# POE_SI3404.net
KiCad netlist of a schematic drawn in Altium Designer
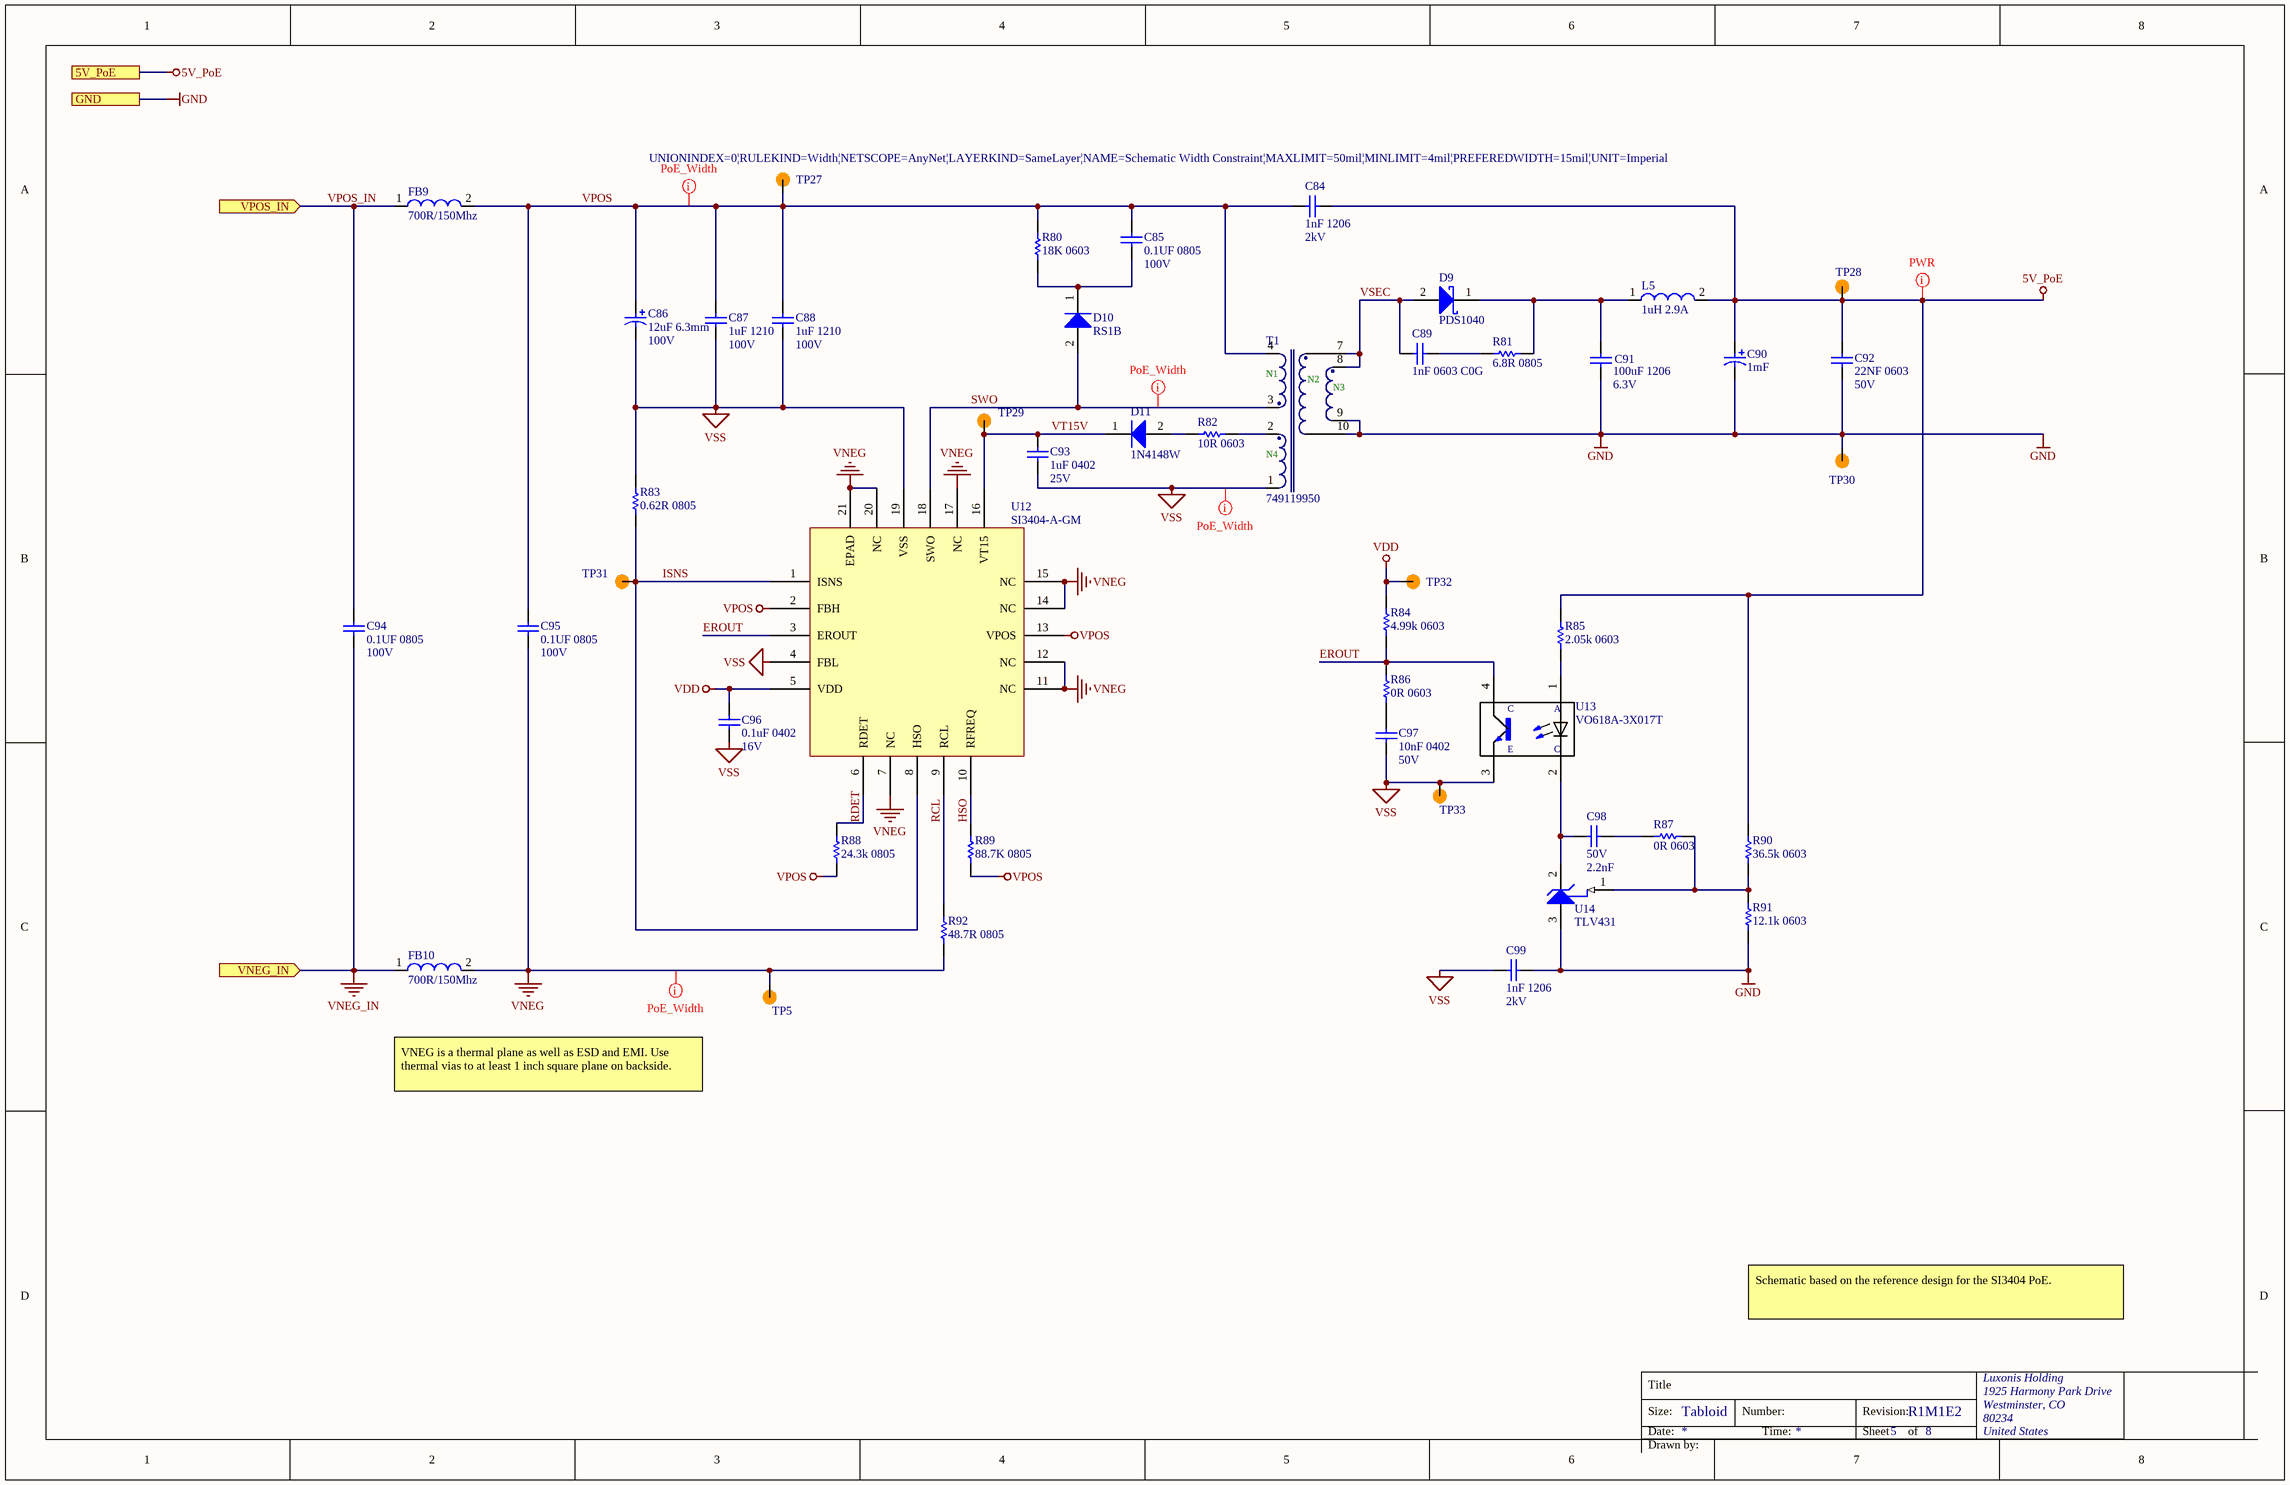
[diagram p0: POE_SI3404.SchDoc]

(export (version "E")
  (design (tool "Eeschema 10.0.6"))
  (components
    (comp (ref "C84")
      (value "1nF 1206")
      (footprint "CAP_Altium_Vault_Generic:CAPC1206(3216)190_N")
      (description "CAP CER 1000PF 2KV X7R 1206")
      (fields (field (name "TOLERANCE") "10%") (field (name "VOLTAGE RATING (DC)") "2kV"))
      (libsource (lib "PCBProject") (part "C1206C102KGRACTU"))
    )
    (comp (ref "C85")
      (value "0.1UF 0805")
      (footprint "CAP_Altium_Vault_Generic:CAPC0805(2012)145_N")
      (description "CAP CER 0.1UF 100V X7R 0805")
      (fields (field (name "TOLERANCE") "10%") (field (name "VOLTAGE RATING") "100V"))
      (libsource (lib "BW2098POE") (part "CL21B104KCFNNNE"))
    )
    (comp (ref "C86")
      (value "12uF 6.3mm")
      (footprint "BW2098POE:EEU-FC2A120")
      (description "CAP ALUM 12UF 20% 100V RADIAL")
      (fields (field (name "TOLERANCE") "20%") (field (name "VOLTAGE") "100V"))
      (libsource (lib "BW2098POE") (part "EEU-FC2A120"))
    )
    (comp (ref "C87")
      (value "1uF 1210")
      (footprint "CAP_Altium_Vault_Generic:CAPC1210(3225)280_N")
      (description "CAP CER 1UF 100V X7R 1210")
      (fields (field (name "TOLERANCE") "10%") (field (name "VOLTAGE RATING") "100V"))
      (libsource (lib "PCBProject") (part "CL32B105KCJNNNE"))
    )
    (comp (ref "C88")
      (value "1uF 1210")
      (footprint "CAP_Altium_Vault_Generic:CAPC1210(3225)280_N")
      (description "CAP CER 1UF 100V X7R 1210")
      (fields (field (name "TOLERANCE") "10%") (field (name "VOLTAGE RATING") "100V"))
      (libsource (lib "PCBProject") (part "CL32B105KCJNNNE"))
    )
    (comp (ref "C89")
      (value "1nF 0603 C0G")
      (footprint "CAP_Altium_Vault_Generic:CAPC0603(1608)100_N")
      (description "CAP CER 1000PF 50V C0G/NP0 0603")
      (fields
        (field (name "MANUFACTURER") "Murata")
        (field (name "MANUFACTURER PART NUMBER") "GRM1885C1H102FA01D")
      )
      (libsource (lib "LuxonisMaster") (part "GRM1885C1H102FA01D"))
    )
    (comp (ref "C90")
      (value "1mF")
      (footprint "ECA-0JM102")
      (description "CAP ALUM 1000UF 6.3V RADIAL 20%")
      (fields (field (name "TOLERANCE") "20%") (field (name "Comment") "ECA-0JM102"))
      (libsource (lib "Luxonis LLC") (part "EEU-FC2A120"))
    )
    (comp (ref "C91")
      (value "100uF 1206")
      (footprint "CAP_Altium_Vault_Generic:CAPC1206(3216)190_N")
      (description "CAP CER 100UF 6.3V X5R 1206")
      (fields (field (name "TOLERANCE") "20%") (field (name "VOLTAGE") "6.3V"))
      (libsource (lib "PCBProject") (part "CL31A107MQHNNNE"))
    )
    (comp (ref "C92")
      (value "22NF 0603")
      (footprint "CAP_Altium_Vault_Generic:CAPC0603(1608)100_N")
      (description "CAP CER 0.022UF 50V X7R 0603")
      (fields (field (name "TOLERANCE") "10%") (field (name "VOLTAGE") "50V"))
      (libsource (lib "LuxonisMaster") (part "C0603C223K5RACTU"))
    )
    (comp (ref "C93")
      (value "1uF 0402")
      (footprint "CAP_Altium_Vault_Generic:CAPC0402(1005)70_N")
      (description "CAP CER 1UF 25V X5R 0402 10%")
      (fields
        (field (name "TOLERANCE") "10%")
        (field (name "VOLTAGE") "25V")
        (field (name "VOLTAGE RATING") "25V")
      )
      (libsource (lib "LuxonisMaster") (part "GRM155R61E105KA12D"))
    )
    (comp (ref "C94")
      (value "0.1UF 0805")
      (footprint "CAP_Altium_Vault_Generic:CAPC0805(2012)145_N")
      (description "CAP CER 0.1UF 100V X7R 0805")
      (fields (field (name "TOLERANCE") "10%") (field (name "VOLTAGE RATING") "100V"))
      (libsource (lib "PCBProject") (part "CL21B104KCFNNNE"))
    )
    (comp (ref "C95")
      (value "0.1UF 0805")
      (footprint "CAP_Altium_Vault_Generic:CAPC0805(2012)145_N")
      (description "CAP CER 0.1UF 100V X7R 0805")
      (fields (field (name "TOLERANCE") "10%") (field (name "VOLTAGE RATING") "100V"))
      (libsource (lib "PCBProject") (part "CL21B104KCFNNNE"))
    )
    (comp (ref "C96")
      (value "0.1uF 0402")
      (footprint "CAP_Altium_Vault_Generic:CAPC0402(1005)60_N")
      (description "CAP CER 0.1UF 16V X7R 0402")
      (fields (field (name "TOLERANCE") "10%") (field (name "VOLTAGE RATING") "16V"))
      (libsource (lib "PCBProject") (part "CL05B104KO5NFNC"))
    )
    (comp (ref "C97")
      (value "10nF 0402")
      (footprint "CAP_Altium_Vault_Generic:CAPC0402(1005)60_N")
      (description "CAP CER 10000PF 50V X7R 0402")
      (fields
        (field (name "TOLERANCE") "10%")
        (field (name "VOLTAGE") "25V")
        (field (name "VOLTAGE RATING") "50V")
      )
      (libsource (lib "LuxonisMaster") (part "GRM155R71H103KA88D"))
    )
    (comp (ref "C98")
      (value "2.2nF")
      (footprint "CAPC0603(1608)100_N")
      (description "CAP CER 2200PF 50V C0G 0603 5%")
      (fields
        (field (name "VOLTAGE RATING") "50V")
        (field (name "TOLERANCE") "5%")
        (field (name "Comment") "GRM1885C1H222JA01D")
      )
      (libsource (lib "Luxonis LLC") (part "GRM188R61C475KAAJD"))
    )
    (comp (ref "C99")
      (value "1nF 1206")
      (footprint "CAP_Altium_Vault_Generic:CAPC1206(3216)190_N")
      (description "CAP CER 1000PF 2KV X7R 1206")
      (fields (field (name "TOLERANCE") "10%") (field (name "VOLTAGE RATING (DC)") "2kV"))
      (libsource (lib "PCBProject") (part "C1206C102KGRACTU"))
    )
    (comp (ref "D9")
      (value "PDS1040")
      (footprint "BW2098POE:PDS1040-13")
      (description "DIODE SCHOTTKY 40V 10A POWERDI5")
      (libsource (lib "PCBProject") (part "PDS1040-13"))
    )
    (comp (ref "D10")
      (value "RS1B")
      (footprint "BW2098POE:RS1B")
      (description "DIODE GEN PURP 100V 1A SMA")
      (libsource (lib "BW2098POE") (part "RS1B"))
    )
    (comp (ref "D11")
      (value "1N4148W")
      (footprint "BW2098POE:1N4148W-7-F")
      (description "DIODE GEN PURP 100V 300MA SOD123")
      (fields (field (name "VOLTAGE") "100V"))
      (libsource (lib "PCBProject") (part "1N4148W-7-F"))
    )
    (comp (ref "FB9")
      (value "700R/150Mhz")
      (footprint "BW2098POE:742792040")
      (description "FERRITE BEAD 600 OHM 0805 1LN")
      (fields (field (name "TOLERANCE") "25%"))
      (libsource (lib "BW2098POE") (part "742792040"))
    )
    (comp (ref "FB10")
      (value "700R/150Mhz")
      (footprint "BW2098POE:742792040")
      (description "FERRITE BEAD 600 OHM 0805 1LN")
      (fields (field (name "TOLERANCE") "25%"))
      (libsource (lib "BW2098POE") (part "742792040"))
    )
    (comp (ref "L5")
      (value "1uH 2.9A")
      (footprint "BW2098POE:DO1608C-102MLx")
      (description "IND POWER WIREWOUND 1uH 20% 100KHz FERRITE 2.7A")
      (fields (field (name "TOLERANCE") "20%"))
      (libsource (lib "PCBProject") (part "DO1608C-102ML"))
    )
    (comp (ref "R80")
      (value "18K 0603")
      (footprint "RES_Altium_Vault_Generic:RESC0603(1608)_N")
      (description "RES SMD 18K OHM 5% 1/10W 0603")
      (fields (field (name "TOLERANCE") "5%"))
      (libsource (lib "BW2098POE") (part "RC0603JR-0718KL"))
    )
    (comp (ref "R81")
      (value "6.8R 0805")
      (footprint "RES_Altium_Vault_Generic:RESC0805(2012)_N")
      (description "RES SMD 6.8 OHM 1% 1/8W 0805")
      (fields (field (name "TOLERANCE") "1%"))
      (libsource (lib "BW2098POE") (part "RC0805FR-076R8L"))
    )
    (comp (ref "R82")
      (value "10R 0603")
      (footprint "RES_Altium_Vault_Generic:RESC0603(1608)_N")
      (description "RES SMD 10 OHM 1% 1/10W 0603")
      (fields (field (name "TOLERANCE") "1%"))
      (libsource (lib "PCBProject") (part "CRCW060310R0FKEA"))
    )
    (comp (ref "R83")
      (value "0.62R 0805")
      (footprint "RES_Altium_Vault_Generic:RESC0805(2012)_N")
      (description "RES SMD 620 MOHM 1% 1/8W 0805")
      (fields (field (name "TOLERANCE") "1%"))
      (libsource (lib "BW2098POE") (part "RL0805FR-070R62L"))
    )
    (comp (ref "R84")
      (value "4.99k 0603")
      (footprint "RES_Altium_Vault_Generic:RESC0603(1608)_N")
      (description "RES SMD 4.99K OHM 1% 1/10W 0603")
      (fields (field (name "TOLERANCE") "1%"))
      (libsource (lib "PCBProject") (part "RC0603FR-074K99L"))
    )
    (comp (ref "R85")
      (value "2.05k 0603")
      (footprint "RES_Altium_Vault_Generic:RESC0603(1608)_N")
      (description "RES SMD 2.05K OHM 1% 1/10W 0603")
      (fields (field (name "TOLERANCE") "1%"))
      (libsource (lib "PCBProject") (part "RC0603FR-072K05L"))
    )
    (comp (ref "R86")
      (value "0R 0603")
      (footprint "RES_Altium_Vault_Generic:RESC0603(1608)_N")
      (description "RES SMD 0.0R OHM 1% 1/10W 0603")
      (fields (field (name "TOLERANCE") "5%"))
      (libsource (lib "LuxonisMaster") (part "CRCW06030000Z0EA"))
    )
    (comp (ref "R87")
      (value "0R 0603")
      (footprint "RES_Altium_Vault_Generic:RESC0603(1608)_N")
      (description "RES SMD 0.0R OHM 1% 1/10W 0603")
      (fields (field (name "TOLERANCE") "5%"))
      (libsource (lib "LuxonisMaster") (part "CRCW06030000Z0EA"))
    )
    (comp (ref "R88")
      (value "24.3k 0805")
      (footprint "RES_Altium_Vault_Generic:RESC0805(2012)_N")
      (description "RES SMD 24.3K OHM 1% 1/8W 0805")
      (fields (field (name "TOLERANCE") "1%"))
      (libsource (lib "PCBProject") (part "CRCW080524K3FKEA"))
    )
    (comp (ref "R89")
      (value "88.7K 0805")
      (footprint "RES_Altium_Vault_Generic:RESC0805(2012)_N")
      (description "RES SMD 88.7K OHM 1% 1/8W 0805")
      (fields (field (name "TOLERANCE") "1%"))
      (libsource (lib "BW2098POE") (part "CRCW080588K7FKEA"))
    )
    (comp (ref "R90")
      (value "36.5k 0603")
      (footprint "RES_Altium_Vault_Generic:RESC0603(1608)_N")
      (description "RES SMD 36.5K OHM 1% 1/10W 0603")
      (fields (field (name "TOLERANCE") "1%"))
      (libsource (lib "PCBProject") (part "RC0603FR-0736K5L"))
    )
    (comp (ref "R91")
      (value "12.1k 0603")
      (footprint "RES_Altium_Vault_Generic:RESC0603(1608)_N")
      (description "RES SMD 12.1K OHM 1% 1/10W 0603")
      (fields (field (name "TOLERANCE") "1%"))
      (libsource (lib "PCBProject") (part "RC0603FR-0712K1L"))
    )
    (comp (ref "R92")
      (value "48.7R 0805")
      (footprint "RES_Altium_Vault_Generic:RESC0805(2012)_N")
      (description "RES SMD 48.7 OHM 1% 1/8W 0805")
      (fields (field (name "TOLERANCE") "1%"))
      (libsource (lib "PCBProject") (part "RC0805FR-0748R7L"))
    )
    (comp (ref "T1")
      (value "749119950")
      (footprint "BW2098POE:749119950")
      (description "TRANS FLYBACK POE 127UH SMD")
      (libsource (lib "BW2098POE") (part "749119950"))
    )
    (comp (ref "TP5")
      (value "TP100_200_NS")
      (footprint "TP075_150_NS")
      (libsource (lib "Luxonis LLC") (part "TEST_POINT"))
    )
    (comp (ref "TP27")
      (value "TP100_200_NS")
      (footprint "TP075_150_NS")
      (libsource (lib "Luxonis LLC") (part "TEST_POINT"))
    )
    (comp (ref "TP28")
      (value "TP100_200_NS")
      (footprint "TP075_150_NS")
      (libsource (lib "Luxonis LLC") (part "TEST_POINT"))
    )
    (comp (ref "TP29")
      (value "TP100_200_NS")
      (footprint "TP075_150_NS")
      (libsource (lib "Luxonis LLC") (part "TEST_POINT"))
    )
    (comp (ref "TP30")
      (value "TP100_200_NS")
      (footprint "TP075_150_NS")
      (libsource (lib "Luxonis LLC") (part "TEST_POINT"))
    )
    (comp (ref "TP31")
      (value "TP100_200_NS")
      (footprint "TP075_150_NS")
      (libsource (lib "Luxonis LLC") (part "TEST_POINT"))
    )
    (comp (ref "TP32")
      (value "TP100_200_NS")
      (footprint "TP075_150_NS")
      (libsource (lib "Luxonis LLC") (part "TEST_POINT"))
    )
    (comp (ref "TP33")
      (value "TP100_200_NS")
      (footprint "TP075_150_NS")
      (libsource (lib "Luxonis LLC") (part "TEST_POINT"))
    )
    (comp (ref "U12")
      (value "SI3404-A-GM")
      (footprint "BW2098POE:Si3404-A-GM")
      (description "IC POE CNTRL 1 CHANNEL 20QFN")
      (libsource (lib "BW2098POE") (part "SI3404-A-GM"))
    )
    (comp (ref "U13")
      (value "VO618A-3X017T")
      (footprint "PCBProject:VO618A-3X017T")
      (description "OPTOISOLATOR 5.3KV TRANS 4-SMD")
      (libsource (lib "BW2098POE") (part "VO618A-3X017T"))
    )
    (comp (ref "U14")
      (value "TLV431")
      (footprint "PCBProject:TLV431BCDBZR")
      (description "IC VREF SHUNT ADJ SOT23-3")
      (fields (field (name "TOLERANCE") "0.5%"))
      (libsource (lib "BW2098POE") (part "TLV431BCDBZR"))
    )
  )
  (nets
    (net (code "1") (name "/EROUT") (class "Default")
      (node (ref "R84") (pin "1") (pinfunction "1_1") (pintype "passive"))
      (node (ref "R86") (pin "2") (pinfunction "2_2") (pintype "passive"))
      (node (ref "U12") (pin "3") (pinfunction "EROUT_3") (pintype "passive"))
      (node (ref "U13") (pin "4") (pinfunction "CO_4") (pintype "passive"))
    )
    (net (code "2") (name "/HSO") (class "Default")
      (node (ref "R89") (pin "2") (pinfunction "2_2") (pintype "passive"))
      (node (ref "U12") (pin "10") (pinfunction "RFREQ_10") (pintype "passive"))
    )
    (net (code "3") (name "/ISNS") (class "Default")
      (node (ref "R83") (pin "1") (pinfunction "1_1") (pintype "passive"))
      (node (ref "TP31") (pin "1") (pintype "passive"))
      (node (ref "U12") (pin "1") (pinfunction "ISNS_1") (pintype "passive"))
      (node (ref "U12") (pin "8") (pinfunction "HSO_8") (pintype "passive"))
    )
    (net (code "4") (name "/RCL") (class "Default")
      (node (ref "R92") (pin "2") (pinfunction "2_2") (pintype "passive"))
      (node (ref "U12") (pin "9") (pinfunction "RCL_9") (pintype "passive"))
    )
    (net (code "5") (name "/RDET") (class "Default")
      (node (ref "R88") (pin "2") (pinfunction "2_2") (pintype "passive"))
      (node (ref "U12") (pin "6") (pinfunction "RDET_6") (pintype "passive"))
    )
    (net (code "6") (name "/SWO") (class "Default")
      (node (ref "D10") (pin "2") (pinfunction "A_2") (pintype "passive"))
      (node (ref "T1") (pin "3") (pinfunction "3_3") (pintype "passive"))
      (node (ref "U12") (pin "18") (pinfunction "SWO_18") (pintype "passive"))
    )
    (net (code "7") (name "/VPOS_IN") (class "Default")
      (node (ref "C94") (pin "2") (pinfunction "2_2") (pintype "passive"))
      (node (ref "FB9") (pin "1") (pinfunction "1_1") (pintype "passive"))
    )
    (net (code "8") (name "/VSEC") (class "Default")
      (node (ref "C89") (pin "2") (pinfunction "2_2") (pintype "passive"))
      (node (ref "D9") (pin "2") (pinfunction "A_2") (pintype "passive"))
      (node (ref "T1") (pin "7") (pinfunction "7_7") (pintype "passive"))
      (node (ref "T1") (pin "8") (pinfunction "8_8") (pintype "passive"))
    )
    (net (code "9") (name "/VT15V") (class "Default")
      (node (ref "C93") (pin "2") (pinfunction "2_2") (pintype "passive"))
      (node (ref "D11") (pin "1") (pinfunction "K_1") (pintype "passive"))
      (node (ref "TP29") (pin "1") (pintype "passive"))
      (node (ref "U12") (pin "16") (pinfunction "VT15_16") (pintype "passive"))
    )
    (net (code "10") (name "5V_PoE") (class "Default")
      (node (ref "C84") (pin "2") (pinfunction "2_2") (pintype "passive"))
      (node (ref "C90") (pin "1") (pinfunction "1_1") (pintype "passive"))
      (node (ref "C92") (pin "2") (pinfunction "2_2") (pintype "passive"))
      (node (ref "L5") (pin "2") (pinfunction "2_2") (pintype "passive"))
      (node (ref "R85") (pin "2") (pinfunction "2_2") (pintype "passive"))
      (node (ref "R90") (pin "2") (pinfunction "2_2") (pintype "passive"))
      (node (ref "TP28") (pin "1") (pintype "passive"))
    )
    (net (code "11") (name "GND") (class "Default")
      (node (ref "C90") (pin "2") (pinfunction "2_2") (pintype "passive"))
      (node (ref "C91") (pin "1") (pinfunction "1_1") (pintype "passive"))
      (node (ref "C92") (pin "1") (pinfunction "1_1") (pintype "passive"))
      (node (ref "C99") (pin "2") (pinfunction "2_2") (pintype "passive"))
      (node (ref "R91") (pin "1") (pinfunction "1_1") (pintype "passive"))
      (node (ref "T1") (pin "10") (pinfunction "10_10") (pintype "passive"))
      (node (ref "T1") (pin "9") (pinfunction "9_9") (pintype "passive"))
      (node (ref "TP30") (pin "1") (pintype "passive"))
      (node (ref "U14") (pin "3") (pinfunction "ANODE_3") (pintype "passive"))
    )
    (net (code "12") (name "Net-(C89-Pad1)") (class "Default")
      (node (ref "C89") (pin "1") (pinfunction "1_1") (pintype "passive"))
      (node (ref "R81") (pin "1") (pinfunction "1_1") (pintype "passive"))
    )
    (net (code "13") (name "Net-(C97-Pad2)") (class "Default")
      (node (ref "C97") (pin "2") (pinfunction "2_2") (pintype "passive"))
      (node (ref "R86") (pin "1") (pinfunction "1_1") (pintype "passive"))
    )
    (net (code "14") (name "Net-(C98-Pad2)") (class "Default")
      (node (ref "C98") (pin "2") (pinfunction "2_2") (pintype "passive"))
      (node (ref "R87") (pin "2") (pinfunction "2_2") (pintype "passive"))
    )
    (net (code "15") (name "Net-(D9-K)") (class "Default")
      (node (ref "C91") (pin "2") (pinfunction "2_2") (pintype "passive"))
      (node (ref "D9") (pin "1") (pinfunction "K_1") (pintype "passive"))
      (node (ref "L5") (pin "1") (pinfunction "1_1") (pintype "passive"))
      (node (ref "R81") (pin "2") (pinfunction "2_2") (pintype "passive"))
    )
    (net (code "16") (name "Net-(D10-K)") (class "Default")
      (node (ref "C85") (pin "1") (pinfunction "1_1") (pintype "passive"))
      (node (ref "D10") (pin "1") (pinfunction "K_1") (pintype "passive"))
      (node (ref "R80") (pin "1") (pinfunction "1_1") (pintype "passive"))
    )
    (net (code "17") (name "Net-(D11-A)") (class "Default")
      (node (ref "D11") (pin "2") (pinfunction "A_2") (pintype "passive"))
      (node (ref "R82") (pin "1") (pinfunction "1_1") (pintype "passive"))
    )
    (net (code "18") (name "Net-(R82-Pad2)") (class "Default")
      (node (ref "R82") (pin "2") (pinfunction "2_2") (pintype "passive"))
      (node (ref "T1") (pin "2") (pinfunction "2_2") (pintype "passive"))
    )
    (net (code "19") (name "Net-(U13-A)") (class "Default")
      (node (ref "R85") (pin "1") (pinfunction "1_1") (pintype "passive"))
      (node (ref "U13") (pin "1") (pinfunction "A_1") (pintype "passive"))
    )
    (net (code "20") (name "Net-(U13-C)") (class "Default")
      (node (ref "C98") (pin "1") (pinfunction "1_1") (pintype "passive"))
      (node (ref "U13") (pin "2") (pinfunction "C_2") (pintype "passive"))
      (node (ref "U14") (pin "2") (pinfunction "CATHODE_2") (pintype "passive"))
    )
    (net (code "21") (name "Net-(U14-REF)") (class "Default")
      (node (ref "R87") (pin "1") (pinfunction "1_1") (pintype "passive"))
      (node (ref "R90") (pin "1") (pinfunction "1_1") (pintype "passive"))
      (node (ref "R91") (pin "2") (pinfunction "2_2") (pintype "passive"))
      (node (ref "U14") (pin "1") (pinfunction "REF_1") (pintype "input"))
    )
    (net (code "22") (name "VDD") (class "Default")
      (node (ref "C96") (pin "2") (pinfunction "2_2") (pintype "passive"))
      (node (ref "R84") (pin "2") (pinfunction "2_2") (pintype "passive"))
      (node (ref "TP32") (pin "1") (pintype "passive"))
      (node (ref "U12") (pin "5") (pinfunction "VDD_5") (pintype "passive"))
    )
    (net (code "23") (name "VNEG") (class "Default")
      (node (ref "C95") (pin "1") (pinfunction "1_1") (pintype "passive"))
      (node (ref "FB10") (pin "2") (pinfunction "2_2") (pintype "passive"))
      (node (ref "R92") (pin "1") (pinfunction "1_1") (pintype "passive"))
      (node (ref "TP5") (pin "1") (pintype "passive"))
      (node (ref "U12") (pin "11") (pinfunction "NC_11") (pintype "passive"))
      (node (ref "U12") (pin "12") (pinfunction "NC_12") (pintype "passive"))
      (node (ref "U12") (pin "14") (pinfunction "NC_14") (pintype "passive"))
      (node (ref "U12") (pin "15") (pinfunction "NC_15") (pintype "passive"))
      (node (ref "U12") (pin "17") (pinfunction "NC_17") (pintype "passive"))
      (node (ref "U12") (pin "20") (pinfunction "NC_20") (pintype "passive"))
      (node (ref "U12") (pin "21") (pinfunction "EPAD_21") (pintype "passive"))
      (node (ref "U12") (pin "7") (pinfunction "NC_7") (pintype "passive"))
    )
    (net (code "24") (name "VNEG_IN") (class "Default")
      (node (ref "C94") (pin "1") (pinfunction "1_1") (pintype "passive"))
      (node (ref "FB10") (pin "1") (pinfunction "1_1") (pintype "passive"))
    )
    (net (code "25") (name "VPOS") (class "Default")
      (node (ref "C84") (pin "1") (pinfunction "1_1") (pintype "passive"))
      (node (ref "C85") (pin "2") (pinfunction "2_2") (pintype "passive"))
      (node (ref "C86") (pin "1") (pinfunction "1_1") (pintype "passive"))
      (node (ref "C87") (pin "2") (pinfunction "2_2") (pintype "passive"))
      (node (ref "C88") (pin "2") (pinfunction "2_2") (pintype "passive"))
      (node (ref "C95") (pin "2") (pinfunction "2_2") (pintype "passive"))
      (node (ref "FB9") (pin "2") (pinfunction "2_2") (pintype "passive"))
      (node (ref "R80") (pin "2") (pinfunction "2_2") (pintype "passive"))
      (node (ref "R88") (pin "1") (pinfunction "1_1") (pintype "passive"))
      (node (ref "R89") (pin "1") (pinfunction "1_1") (pintype "passive"))
      (node (ref "T1") (pin "4") (pinfunction "4_4") (pintype "passive"))
      (node (ref "TP27") (pin "1") (pintype "passive"))
      (node (ref "U12") (pin "13") (pinfunction "VPOS_13") (pintype "passive"))
      (node (ref "U12") (pin "2") (pinfunction "FBH_2") (pintype "passive"))
    )
    (net (code "26") (name "VSS") (class "Default")
      (node (ref "C86") (pin "2") (pinfunction "2_2") (pintype "passive"))
      (node (ref "C87") (pin "1") (pinfunction "1_1") (pintype "passive"))
      (node (ref "C88") (pin "1") (pinfunction "1_1") (pintype "passive"))
      (node (ref "C93") (pin "1") (pinfunction "1_1") (pintype "passive"))
      (node (ref "C96") (pin "1") (pinfunction "1_1") (pintype "passive"))
      (node (ref "C97") (pin "1") (pinfunction "1_1") (pintype "passive"))
      (node (ref "C99") (pin "1") (pinfunction "1_1") (pintype "passive"))
      (node (ref "R83") (pin "2") (pinfunction "2_2") (pintype "passive"))
      (node (ref "T1") (pin "1") (pinfunction "1_1") (pintype "passive"))
      (node (ref "TP33") (pin "1") (pintype "passive"))
      (node (ref "U12") (pin "19") (pinfunction "VSS_19") (pintype "passive"))
      (node (ref "U12") (pin "4") (pinfunction "FBL_4") (pintype "passive"))
      (node (ref "U13") (pin "3") (pinfunction "E_3") (pintype "passive"))
    )
  )
)
